# Power.net
KiCad netlist of a schematic drawn in Altium Designer
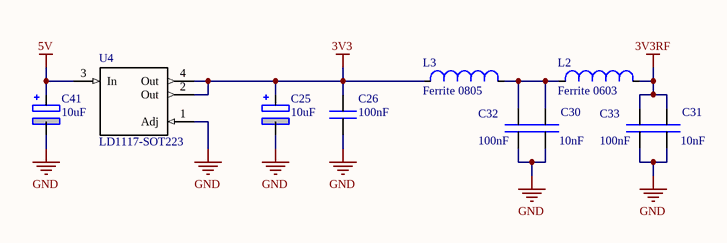
[diagram p0: Power.SchDoc]

(export (version "E")
  (design (tool "Eeschema 10.0.6"))
  (components
    (comp (ref "C25")
      (value "10uF")
      (footprint "smd C1206 polar")
      (description "smd capaciteit, tantalium, verp.1206, 10uF/10V")
      (fields (field (name "PART NUMBER") "CSMD1206/10uF/10V"))
      (libsource (lib "CDE_Library") (part "CSMD1206/10uF/10V"))
    )
    (comp (ref "C26")
      (value "100nF")
      (footprint "smd C0603_0.80")
      (description "smd capaciteit, verp.0603, 100nF")
      (fields (field (name "PART NUMBER") "CSMD603/100nF"))
      (libsource (lib "CDE_Library") (part "CSMD603/100nF"))
    )
    (comp (ref "C30")
      (value "10nF")
      (footprint "smd C0402")
      (description "smd capaciteit, verp.0402, 10nF")
      (fields (field (name "PART NUMBER") "CSMD402/100nF"))
      (libsource (lib "CDE_Library") (part "CSMD402/100nF"))
    )
    (comp (ref "C31")
      (value "10nF")
      (footprint "smd C0402")
      (description "smd capaciteit, verp.0402, 10nF")
      (fields (field (name "PART NUMBER") "CSMD402/100nF"))
      (libsource (lib "CDE_Library") (part "CSMD402/100nF"))
    )
    (comp (ref "C32")
      (value "100nF")
      (footprint "smd C0603_0.80")
      (description "smd capaciteit, verp.0603, 100nF")
      (fields (field (name "PART NUMBER") "CSMD603/100nF"))
      (libsource (lib "CDE_Library") (part "CSMD603/100nF"))
    )
    (comp (ref "C33")
      (value "100nF")
      (footprint "smd C0603_0.80")
      (description "smd capaciteit, verp.0603, 100nF")
      (fields (field (name "PART NUMBER") "CSMD603/100nF"))
      (libsource (lib "CDE_Library") (part "CSMD603/100nF"))
    )
    (comp (ref "C41")
      (value "10uF")
      (footprint "smd C1206 polar")
      (description "smd capaciteit, tantalium, verp.1206, 10uF/10V")
      (fields (field (name "PART NUMBER") "CSMD1206/10uF/10V"))
      (libsource (lib "CDE_Library") (part "CSMD1206/10uF/10V"))
    )
    (comp (ref "L2")
      (value "Ferrite 0603")
      (footprint "smd C0603")
      (description "Ferrite bead, 0603 package")
      (libsource (lib "CDE_Library") (part "Ferrite 0603"))
    )
    (comp (ref "L3")
      (value "Ferrite 0805")
      (footprint "smd C0805")
      (description "Ferrite bead, 0805 package")
      (libsource (lib "CDE_Library") (part "Ferrite 0805"))
    )
    (comp (ref "U4")
      (value "LD1117-SOT223")
      (footprint "SOT223")
      (libsource (lib "vh_altium_library") (part "LD1117-SOT223"))
    )
  )
  (nets
    (net (code "1") (name "3V3") (class "Default")
      (node (ref "C25") (pin "1") (pintype "passive"))
      (node (ref "C26") (pin "2") (pintype "passive"))
      (node (ref "L3") (pin "1") (pintype "passive"))
      (node (ref "U4") (pin "2") (pinfunction "Out_2") (pintype "output"))
      (node (ref "U4") (pin "4") (pinfunction "Out_4") (pintype "output"))
    )
    (net (code "2") (name "3V3RF") (class "Default")
      (node (ref "C31") (pin "2") (pintype "passive"))
      (node (ref "C33") (pin "2") (pintype "passive"))
      (node (ref "L2") (pin "2") (pintype "passive"))
    )
    (net (code "3") (name "5V") (class "Default")
      (node (ref "C41") (pin "1") (pintype "passive"))
      (node (ref "U4") (pin "3") (pinfunction "In_3") (pintype "input"))
    )
    (net (code "4") (name "GND") (class "Default")
      (node (ref "C25") (pin "2") (pintype "passive"))
      (node (ref "C26") (pin "1") (pintype "passive"))
      (node (ref "C30") (pin "1") (pintype "passive"))
      (node (ref "C31") (pin "1") (pintype "passive"))
      (node (ref "C32") (pin "1") (pintype "passive"))
      (node (ref "C33") (pin "1") (pintype "passive"))
      (node (ref "C41") (pin "2") (pintype "passive"))
      (node (ref "U4") (pin "1") (pinfunction "Adj_1") (pintype "input"))
    )
    (net (code "5") (name "Net-(C30-Pad2)") (class "Default")
      (node (ref "C30") (pin "2") (pintype "passive"))
      (node (ref "C32") (pin "2") (pintype "passive"))
      (node (ref "L2") (pin "1") (pintype "passive"))
      (node (ref "L3") (pin "2") (pintype "passive"))
    )
  )
)
